# Simple-Transmitter-2N918.net
KiCad netlist of a schematic drawn in EAGLE
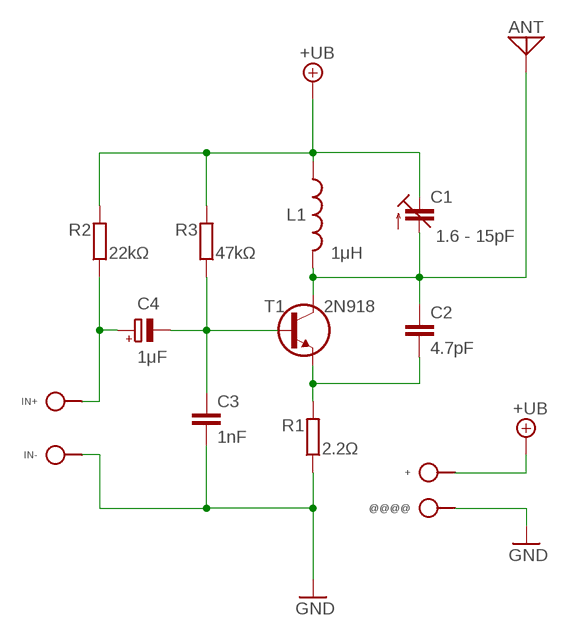
[diagram p0: schematic, sheet 1]

(export (version "E")
  (design (tool "Eeschema 10.0.6"))
  (components
    (comp (ref "+")
      (value "SPAD")
      (footprint "eagle-import:SPAD")
      (libsource (lib "eagle-import") (part "SPAD"))
    )
    (comp (ref "@@@@")
      (value "SPAD")
      (footprint "eagle-import:SPAD")
      (libsource (lib "eagle-import") (part "SPAD"))
    )
    (comp (ref "ANT")
      (value "ANT")
      (footprint "eagle-import:SPAD")
      (libsource (lib "eagle-import") (part "ANT"))
    )
    (comp (ref "C1")
      (value "1.6 - 15pF")
      (footprint "eagle-import:TRIM-2222-808")
      (libsource (lib "eagle-import") (part "C-TR-PH201272222-808-2PINB"))
    )
    (comp (ref "C2")
      (value "4.7pF")
      (footprint "eagle-import:C025-020X036")
      (libsource (lib "eagle-import") (part "C025-020X036"))
    )
    (comp (ref "C3")
      (value "1nF")
      (footprint "eagle-import:C025-020X036")
      (libsource (lib "eagle-import") (part "C025-020X036"))
    )
    (comp (ref "C4")
      (value "1μF")
      (footprint "eagle-import:E2,5-3")
      (libsource (lib "eagle-import") (part "CPOLE2,5-3"))
    )
    (comp (ref "IN+")
      (value "SPAD")
      (footprint "eagle-import:SPAD")
      (libsource (lib "eagle-import") (part "SPAD"))
    )
    (comp (ref "IN-")
      (value "SPAD")
      (footprint "eagle-import:SPAD")
      (libsource (lib "eagle-import") (part "SPAD"))
    )
    (comp (ref "L1")
      (value "1μH")
      (footprint "eagle-import:L-04_7")
      (libsource (lib "eagle-import") (part "L04/7"))
    )
    (comp (ref "R1")
      (value "2.2Ω")
      (footprint "eagle-import:0202V")
      (libsource (lib "eagle-import") (part "R0202V"))
    )
    (comp (ref "R2")
      (value "22kΩ")
      (footprint "eagle-import:0202_5")
      (libsource (lib "eagle-import") (part "R0202/5"))
    )
    (comp (ref "R3")
      (value "47kΩ")
      (footprint "eagle-import:0202_5")
      (libsource (lib "eagle-import") (part "R0202/5"))
    )
    (comp (ref "T1")
      (value "2N918")
      (footprint "eagle-import:TO-72")
      (libsource (lib "eagle-import") (part "2N918TO-72-CE"))
    )
  )
  (nets
    (net (code "1") (name "+UB") (class "Default")
      (node (ref "+") (pin "1") (pinfunction "P$1_1") (pintype "bidirectional"))
      (node (ref "C1") (pin "3") (pinfunction "A_3") (pintype "passive"))
      (node (ref "L1") (pin "1") (pinfunction "1_1") (pintype "passive"))
      (node (ref "R2") (pin "2") (pinfunction "2_2") (pintype "passive"))
      (node (ref "R3") (pin "2") (pinfunction "2_2") (pintype "passive"))
    )
    (net (code "2") (name "GND") (class "Default")
      (node (ref "@@@@") (pin "1") (pinfunction "P$1_1") (pintype "bidirectional"))
      (node (ref "C3") (pin "2") (pinfunction "2_2") (pintype "passive"))
      (node (ref "IN-") (pin "1") (pinfunction "P$1_1") (pintype "bidirectional"))
      (node (ref "R1") (pin "1") (pinfunction "1_1") (pintype "passive"))
    )
    (net (code "3") (name "Net-(C1-E)") (class "Default")
      (node (ref "ANT") (pin "1") (pinfunction "1_1") (pintype "output"))
      (node (ref "C1") (pin "2") (pinfunction "E_2") (pintype "passive"))
      (node (ref "C2") (pin "1") (pinfunction "1_1") (pintype "passive"))
      (node (ref "L1") (pin "2") (pinfunction "2_2") (pintype "passive"))
      (node (ref "T1") (pin "3") (pinfunction "C_3") (pintype "passive"))
    )
    (net (code "4") (name "Net-(C2-Pad2)") (class "Default")
      (node (ref "C2") (pin "2") (pinfunction "2_2") (pintype "passive"))
      (node (ref "R1") (pin "2") (pinfunction "2_2") (pintype "passive"))
      (node (ref "T1") (pin "1") (pinfunction "E_1") (pintype "passive"))
      (node (ref "T1") (pin "4") (pinfunction "E_4") (pintype "passive"))
    )
    (net (code "5") (name "Net-(IN+-P$1)") (class "Default")
      (node (ref "C4") (pin "+") (pinfunction "+_+") (pintype "passive"))
      (node (ref "IN+") (pin "1") (pinfunction "P$1_1") (pintype "bidirectional"))
      (node (ref "R2") (pin "1") (pinfunction "1_1") (pintype "passive"))
    )
    (net (code "6") (name "Net-(T1-B)") (class "Default")
      (node (ref "C3") (pin "1") (pinfunction "1_1") (pintype "passive"))
      (node (ref "C4") (pin "-") (pinfunction "-_-") (pintype "passive"))
      (node (ref "R3") (pin "1") (pinfunction "1_1") (pintype "passive"))
      (node (ref "T1") (pin "2") (pinfunction "B_2") (pintype "passive"))
    )
  )
)
